# Perifericos.net
KiCad netlist of a schematic drawn in Altium Designer
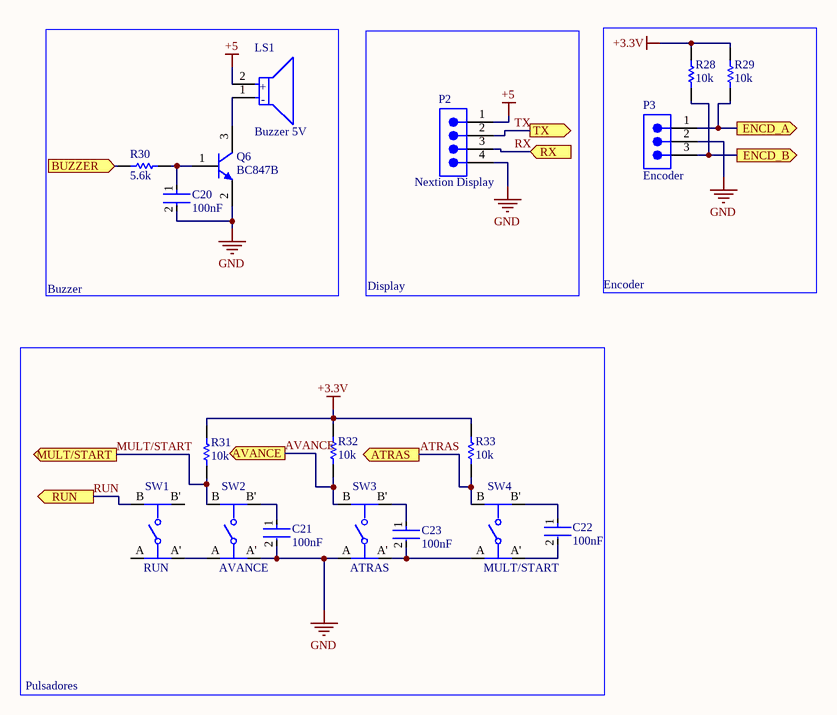
[diagram p0: Perifericos.SchDoc]

(export (version "E")
  (design (tool "Eeschema 10.0.6"))
  (components
    (comp (ref "C20")
      (value "100nF")
      (footprint "FP-0805-L_2_01_0_2-W_1_25-IPC_B")
      (description "General Purpose Ceramic Capacitor, 0805, 100nF, 10%, X7R, 15%, 100V")
      (fields (field (name "VOLTAGE") "100V") (field (name "TOLERANCE") "10%"))
      (libsource (lib "Altium Content Vault") (part "b4654b650e69147ec39a6b967a45e02"))
    )
    (comp (ref "C21")
      (value "100nF")
      (footprint "FP-0805-L_2_01_0_2-W_1_25-IPC_B")
      (description "General Purpose Ceramic Capacitor, 0805, 100nF, 10%, X7R, 15%, 100V")
      (fields (field (name "VOLTAGE") "100V") (field (name "TOLERANCE") "10%"))
      (libsource (lib "Altium Content Vault") (part "b4654b650e69147ec39a6b967a45e02"))
    )
    (comp (ref "C22")
      (value "100nF")
      (footprint "FP-0805-L_2_01_0_2-W_1_25-IPC_B")
      (description "General Purpose Ceramic Capacitor, 0805, 100nF, 10%, X7R, 15%, 100V")
      (fields (field (name "VOLTAGE") "100V") (field (name "TOLERANCE") "10%"))
      (libsource (lib "Altium Content Vault") (part "b4654b650e69147ec39a6b967a45e02"))
    )
    (comp (ref "C23")
      (value "100nF")
      (footprint "FP-0805-L_2_01_0_2-W_1_25-IPC_B")
      (description "General Purpose Ceramic Capacitor, 0805, 100nF, 10%, X7R, 15%, 100V")
      (fields (field (name "VOLTAGE") "100V") (field (name "TOLERANCE") "10%"))
      (libsource (lib "Altium Content Vault") (part "b4654b650e69147ec39a6b967a45e02"))
    )
    (comp (ref "LS1")
      (value "Buzzer 5V")
      (footprint "FP-SDC1610M5-01-MFG")
      (description "AUDIO MAGNETIC INDICATOR 4-8V TH")
      (libsource (lib "Altium Content Vault") (part "f7ec632b6fea80cbef86dc3340f200c"))
    )
    (comp (ref "P2")
      (value "Nextion Display")
      (footprint "61300411121")
      (libsource (lib "Altium Content Vault") (part "Header_Male_1R_04P"))
    )
    (comp (ref "P3")
      (value "Encoder")
      (footprint "61300311121")
      (libsource (lib "Altium Content Vault") (part "Header_Male_1R_03P"))
    )
    (comp (ref "Q6")
      (value "BC847B")
      (footprint "INF-SOT23_M")
      (description "NPN Silicon AF Transistor, 45 V VCEO, 100 mA IC, SOT23, Reel, Green")
      (fields (field (name "MANUFACTURER") "Infineon"))
      (libsource (lib "Altium Content Vault") (part "INF-BJTNPN-BEC-3"))
    )
    (comp (ref "R28")
      (value "10k")
      (footprint "RESC2013X50X30LL20T20")
      (fields (field (name "MANUFACTURER") "Vishay Dale") (field (name "PART NUMBER") "CRCW08050000Z0EA"))
      (libsource (lib "Altium Content Vault") (part "RES"))
    )
    (comp (ref "R29")
      (value "10k")
      (footprint "RESC2013X50X30LL20T20")
      (fields (field (name "MANUFACTURER") "Vishay Dale") (field (name "PART NUMBER") "CRCW08050000Z0EA"))
      (libsource (lib "Altium Content Vault") (part "RES"))
    )
    (comp (ref "R30")
      (value "5.6k")
      (footprint "RESC2013X50X30NL20T20")
      (fields (field (name "MANUFACTURER") "Vishay Dale") (field (name "PART NUMBER") "CRCW08050000Z0EA"))
      (libsource (lib "Altium Content Vault") (part "RES"))
    )
    (comp (ref "R31")
      (value "10k")
      (footprint "RESC2013X50X30LL20T20")
      (fields (field (name "MANUFACTURER") "Vishay Dale") (field (name "PART NUMBER") "CRCW08050000Z0EA"))
      (libsource (lib "Altium Content Vault") (part "RES"))
    )
    (comp (ref "R32")
      (value "10k")
      (footprint "RESC2013X50X30LL20T20")
      (fields (field (name "MANUFACTURER") "Vishay Dale") (field (name "PART NUMBER") "CRCW08050000Z0EA"))
      (libsource (lib "Altium Content Vault") (part "RES"))
    )
    (comp (ref "R33")
      (value "10k")
      (footprint "RESC2013X50X30LL20T20")
      (fields (field (name "MANUFACTURER") "Vishay Dale") (field (name "PART NUMBER") "CRCW08050000Z0EA"))
      (libsource (lib "Altium Content Vault") (part "RES"))
    )
    (comp (ref "SW1")
      (value "RUN")
      (footprint "FP-EVQ-PAC07K-MFG")
      (description "EVQ-PAC07K Switch Tactile N.O. SPST Round Button PC Pins 0.02A 15VDC 1N Thru-Hole Bulk")
      (libsource (lib "Altium Content Vault") (part "841f23923f71b23f3ea0ab5dfb78dcc"))
    )
    (comp (ref "SW2")
      (value "AVANCE")
      (footprint "FP-EVQ-PAC07K-MFG")
      (description "EVQ-PAC07K Switch Tactile N.O. SPST Round Button PC Pins 0.02A 15VDC 1N Thru-Hole Bulk")
      (libsource (lib "Altium Content Vault") (part "841f23923f71b23f3ea0ab5dfb78dcc"))
    )
    (comp (ref "SW3")
      (value "ATRAS")
      (footprint "FP-EVQ-PAC07K-MFG")
      (description "EVQ-PAC07K Switch Tactile N.O. SPST Round Button PC Pins 0.02A 15VDC 1N Thru-Hole Bulk")
      (libsource (lib "Altium Content Vault") (part "841f23923f71b23f3ea0ab5dfb78dcc"))
    )
    (comp (ref "SW4")
      (value "MULT/START")
      (footprint "FP-EVQ-PAC07K-MFG")
      (description "EVQ-PAC07K Switch Tactile N.O. SPST Round Button PC Pins 0.02A 15VDC 1N Thru-Hole Bulk")
      (libsource (lib "Altium Content Vault") (part "841f23923f71b23f3ea0ab5dfb78dcc"))
    )
  )
  (nets
    (net (code "1") (name "+3.3V") (class "Default")
      (node (ref "R28") (pin "2") (pinfunction "2_2") (pintype "passive"))
      (node (ref "R29") (pin "2") (pinfunction "2_2") (pintype "passive"))
      (node (ref "R31") (pin "2") (pinfunction "2_2") (pintype "passive"))
      (node (ref "R32") (pin "2") (pinfunction "2_2") (pintype "passive"))
      (node (ref "R33") (pin "2") (pinfunction "2_2") (pintype "passive"))
    )
    (net (code "2") (name "+5") (class "Default")
      (node (ref "LS1") (pin "2") (pinfunction "A_2") (pintype "passive"))
      (node (ref "P2") (pin "1") (pinfunction "1_1") (pintype "passive"))
    )
    (net (code "3") (name "/ATRAS") (class "Default")
      (node (ref "R33") (pin "1") (pinfunction "1_1") (pintype "passive"))
      (node (ref "SW4") (pin "B") (pinfunction "B_B") (pintype "passive"))
    )
    (net (code "4") (name "/AVANCE") (class "Default")
      (node (ref "R32") (pin "1") (pinfunction "1_1") (pintype "passive"))
      (node (ref "SW3") (pin "B") (pinfunction "B_B") (pintype "passive"))
    )
    (net (code "5") (name "/BUZZER") (class "Default")
      (node (ref "R30") (pin "1") (pinfunction "1_1") (pintype "passive"))
    )
    (net (code "6") (name "/ENCD_A") (class "Default")
      (node (ref "P3") (pin "1") (pinfunction "1_1") (pintype "passive"))
      (node (ref "R29") (pin "1") (pinfunction "1_1") (pintype "passive"))
    )
    (net (code "7") (name "/ENCD_B") (class "Default")
      (node (ref "P3") (pin "3") (pinfunction "3_3") (pintype "passive"))
      (node (ref "R28") (pin "1") (pinfunction "1_1") (pintype "passive"))
    )
    (net (code "8") (name "/MULT{slash}START") (class "Default")
      (node (ref "R31") (pin "1") (pinfunction "1_1") (pintype "passive"))
      (node (ref "SW2") (pin "B") (pinfunction "B_B") (pintype "passive"))
    )
    (net (code "9") (name "/RUN") (class "Default")
      (node (ref "SW1") (pin "B") (pinfunction "B_B") (pintype "passive"))
    )
    (net (code "10") (name "/RX") (class "Default")
      (node (ref "P2") (pin "3") (pinfunction "3_3") (pintype "passive"))
    )
    (net (code "11") (name "/TX") (class "Default")
      (node (ref "P2") (pin "2") (pinfunction "2_2") (pintype "passive"))
    )
    (net (code "12") (name "GND") (class "Default")
      (node (ref "C20") (pin "2") (pinfunction "2_2") (pintype "passive"))
      (node (ref "C21") (pin "2") (pinfunction "2_2") (pintype "passive"))
      (node (ref "P2") (pin "4") (pinfunction "4_4") (pintype "passive"))
      (node (ref "P3") (pin "2") (pinfunction "2_2") (pintype "passive"))
      (node (ref "Q6") (pin "2") (pinfunction "E_2") (pintype "passive"))
      (node (ref "SW2") (pin "A'") (pinfunction "A'_A'") (pintype "passive"))
      (node (ref "SW3") (pin "A") (pinfunction "A_A") (pintype "passive"))
    )
    (net (code "13") (name "Net-(C21-Pad1)") (class "Default")
      (node (ref "C21") (pin "1") (pinfunction "1_1") (pintype "passive"))
      (node (ref "SW2") (pin "B'") (pinfunction "B'_B'") (pintype "passive"))
    )
    (net (code "14") (name "Net-(C22-Pad1)") (class "Default")
      (node (ref "C22") (pin "1") (pinfunction "1_1") (pintype "passive"))
      (node (ref "SW4") (pin "B'") (pinfunction "B'_B'") (pintype "passive"))
    )
    (net (code "15") (name "Net-(C22-Pad2)") (class "Default")
      (node (ref "C22") (pin "2") (pinfunction "2_2") (pintype "passive"))
      (node (ref "SW4") (pin "A'") (pinfunction "A'_A'") (pintype "passive"))
    )
    (net (code "16") (name "Net-(C23-Pad1)") (class "Default")
      (node (ref "C23") (pin "1") (pinfunction "1_1") (pintype "passive"))
      (node (ref "SW3") (pin "B'") (pinfunction "B'_B'") (pintype "passive"))
    )
    (net (code "17") (name "Net-(C23-Pad2)") (class "Default")
      (node (ref "C23") (pin "2") (pinfunction "2_2") (pintype "passive"))
      (node (ref "SW3") (pin "A'") (pinfunction "A'_A'") (pintype "passive"))
      (node (ref "SW4") (pin "A") (pinfunction "A_A") (pintype "passive"))
    )
    (net (code "18") (name "Net-(LS1-C)") (class "Default")
      (node (ref "LS1") (pin "1") (pinfunction "C_1") (pintype "passive"))
      (node (ref "Q6") (pin "3") (pinfunction "C_3") (pintype "passive"))
    )
    (net (code "19") (name "Net-(Q6-B)") (class "Default")
      (node (ref "C20") (pin "1") (pinfunction "1_1") (pintype "passive"))
      (node (ref "Q6") (pin "1") (pinfunction "B_1") (pintype "passive"))
      (node (ref "R30") (pin "2") (pinfunction "2_2") (pintype "passive"))
    )
    (net (code "20") (name "Net-(SW1-PadA')") (class "Default")
      (node (ref "SW1") (pin "A'") (pinfunction "A'_A'") (pintype "passive"))
      (node (ref "SW2") (pin "A") (pinfunction "A_A") (pintype "passive"))
    )
    (net (code "21") (name "unconnected-(SW1-PadA)") (class "Default")
      (node (ref "SW1") (pin "A") (pinfunction "A_A") (pintype "passive"))
    )
    (net (code "22") (name "unconnected-(SW1-PadB')") (class "Default")
      (node (ref "SW1") (pin "B'") (pinfunction "B'_B'") (pintype "passive"))
    )
  )
)
